# DDS_Module_r3.net
KiCad netlist of a schematic drawn in EAGLE
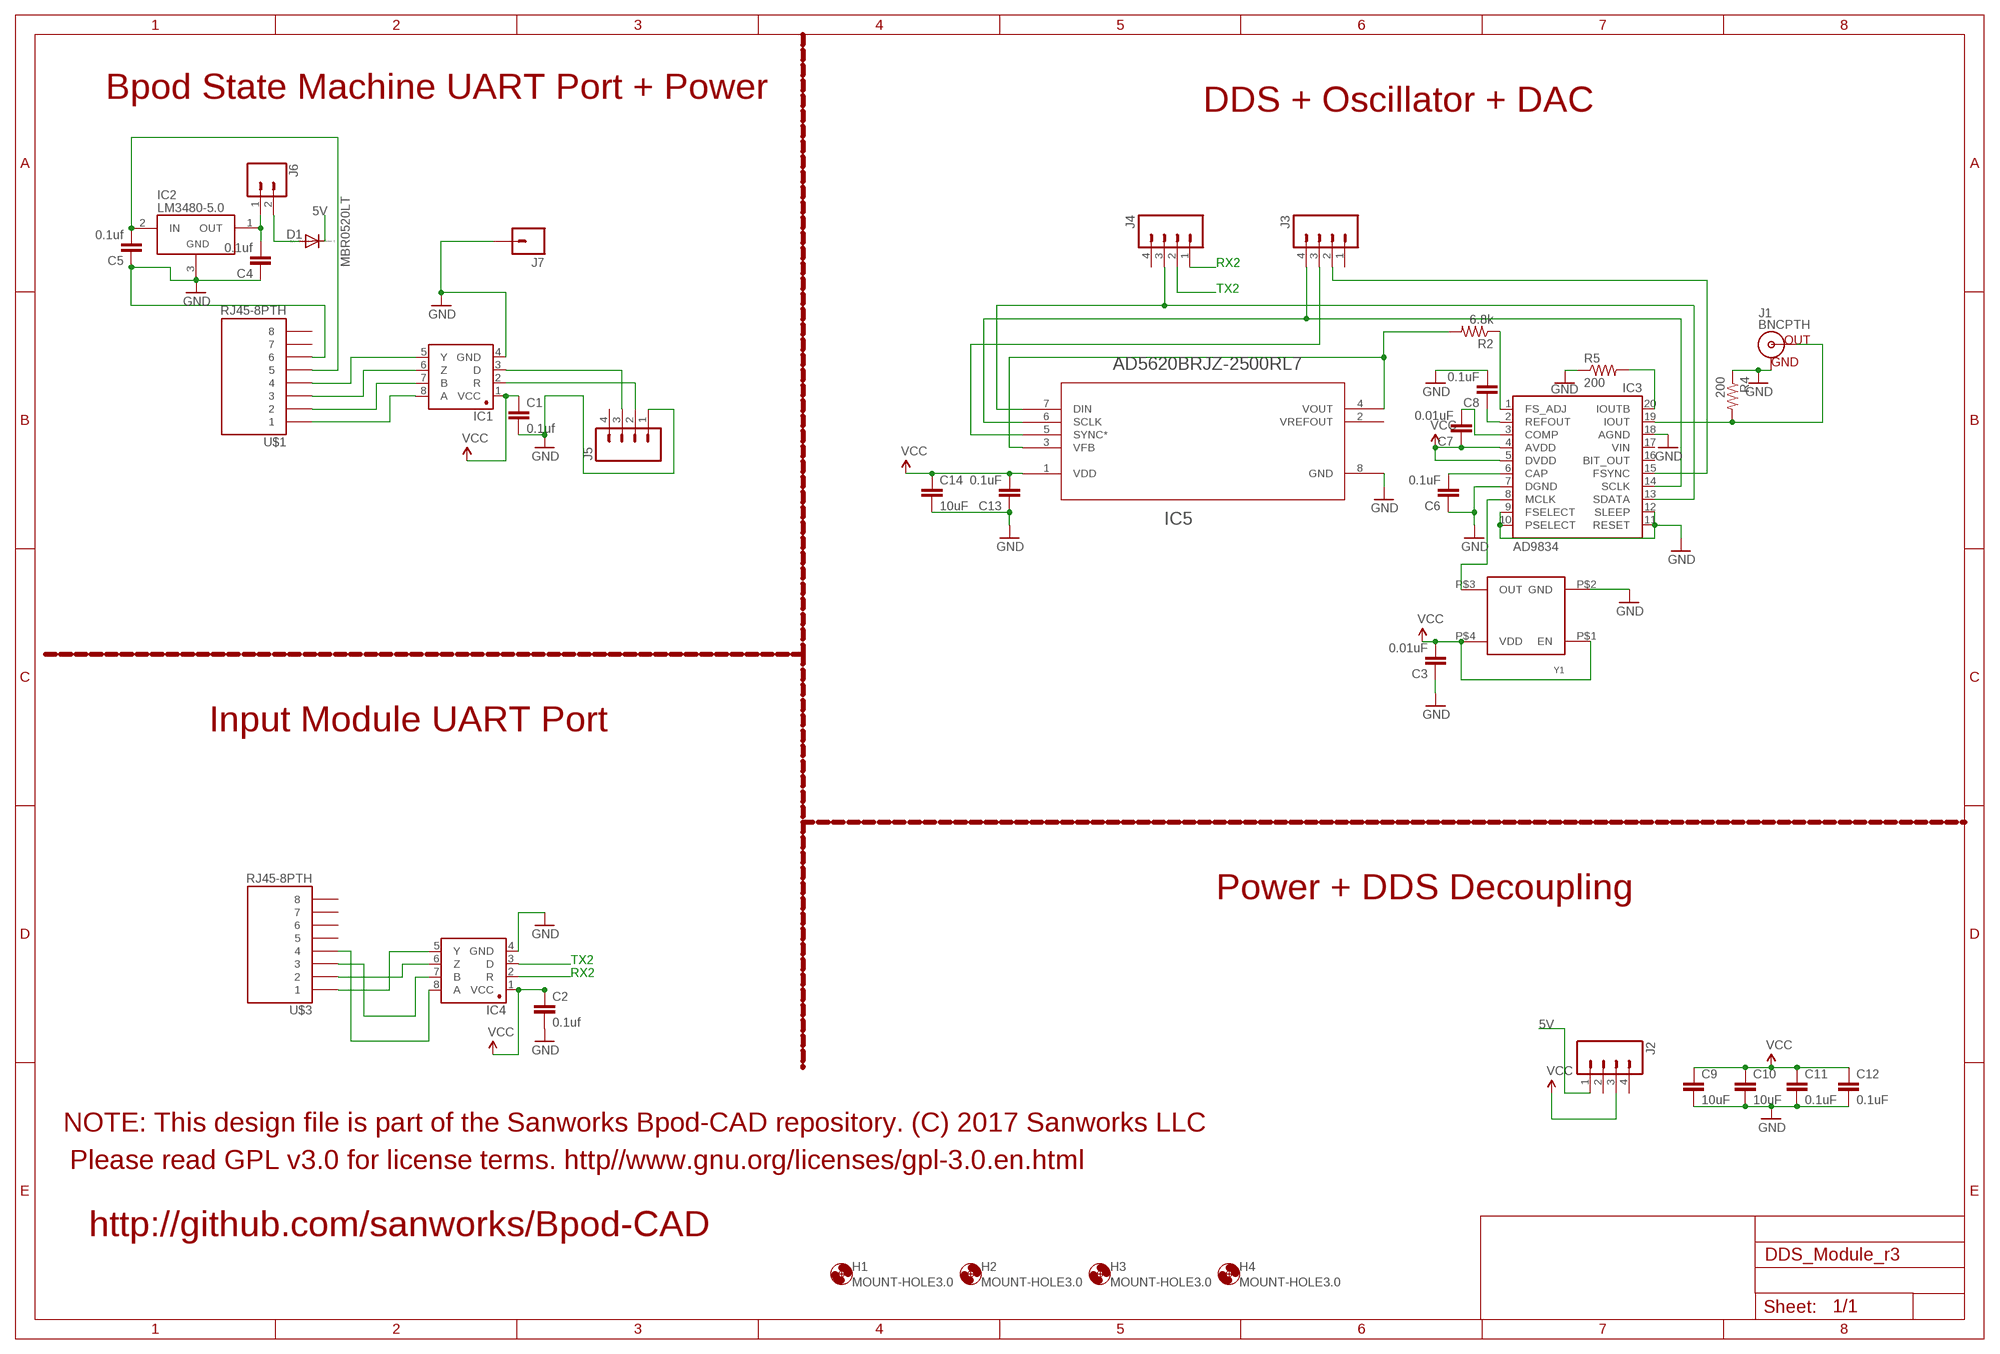
[diagram p0: schematic, sheet 1]

(export (version "E")
  (design (tool "Eeschema 10.0.6"))
  (components
    (comp (ref "C1")
      (value "0.1uf")
      (footprint "eagle-import:1206@1")
      (libsource (lib "eagle-import") (part "CAP1206"))
    )
    (comp (ref "C2")
      (value "0.1uf")
      (footprint "eagle-import:1206@1")
      (libsource (lib "eagle-import") (part "CAP1206"))
    )
    (comp (ref "C3")
      (value "0.01uF")
      (footprint "eagle-import:0805")
      (libsource (lib "eagle-import") (part "10UF-0805-10V-10%"))
    )
    (comp (ref "C4")
      (value "0.1uf")
      (footprint "eagle-import:1206@1")
      (libsource (lib "eagle-import") (part "CAP1206"))
    )
    (comp (ref "C5")
      (value "0.1uf")
      (footprint "eagle-import:1206@1")
      (libsource (lib "eagle-import") (part "CAP1206"))
    )
    (comp (ref "C6")
      (value "0.1uF")
      (footprint "eagle-import:0805")
      (libsource (lib "eagle-import") (part "10UF-0805-10V-10%"))
    )
    (comp (ref "C7")
      (value "0.01uF")
      (footprint "eagle-import:0805")
      (libsource (lib "eagle-import") (part "10UF-0805-10V-10%"))
    )
    (comp (ref "C8")
      (value "0.1uF")
      (footprint "eagle-import:0805")
      (libsource (lib "eagle-import") (part "10UF-0805-10V-10%"))
    )
    (comp (ref "C9")
      (value "10uF")
      (footprint "eagle-import:0805")
      (libsource (lib "eagle-import") (part "10UF-0805-10V-10%"))
    )
    (comp (ref "C10")
      (value "10uF")
      (footprint "eagle-import:0805")
      (libsource (lib "eagle-import") (part "10UF-0805-10V-10%"))
    )
    (comp (ref "C11")
      (value "0.1uF")
      (footprint "eagle-import:0805")
      (libsource (lib "eagle-import") (part "10UF-0805-10V-10%"))
    )
    (comp (ref "C12")
      (value "0.1uF")
      (footprint "eagle-import:0805")
      (libsource (lib "eagle-import") (part "10UF-0805-10V-10%"))
    )
    (comp (ref "C13")
      (value "0.1uF")
      (footprint "eagle-import:0805")
      (libsource (lib "eagle-import") (part "10UF-0805-10V-10%"))
    )
    (comp (ref "C14")
      (value "10uF")
      (footprint "eagle-import:0805")
      (libsource (lib "eagle-import") (part "10UF-0805-10V-10%"))
    )
    (comp (ref "D1")
      (value "MBR0520LT")
      (footprint "eagle-import:SOD123")
      (libsource (lib "eagle-import") (part "MBR0520LT"))
    )
    (comp (ref "H1")
      (value "MOUNT-HOLE3.0")
      (footprint "eagle-import:3,0")
      (libsource (lib "eagle-import") (part "MOUNT-HOLE3.0"))
    )
    (comp (ref "H2")
      (value "MOUNT-HOLE3.0")
      (footprint "eagle-import:3,0")
      (libsource (lib "eagle-import") (part "MOUNT-HOLE3.0"))
    )
    (comp (ref "H3")
      (value "MOUNT-HOLE3.0")
      (footprint "eagle-import:3,0")
      (libsource (lib "eagle-import") (part "MOUNT-HOLE3.0"))
    )
    (comp (ref "H4")
      (value "MOUNT-HOLE3.0")
      (footprint "eagle-import:3,0")
      (libsource (lib "eagle-import") (part "MOUNT-HOLE3.0"))
    )
    (comp (ref "IC1")
      (value "SN65HVD31DR")
      (footprint "eagle-import:SO08")
      (libsource (lib "eagle-import") (part "SN65HVD31DR"))
    )
    (comp (ref "IC2")
      (value "LM3480-5.0")
      (footprint "eagle-import:SOT-23-3")
      (libsource (lib "eagle-import") (part "LM3480-5.0"))
    )
    (comp (ref "IC3")
      (value "AD9834")
      (footprint "eagle-import:TSSOP20")
      (libsource (lib "eagle-import") (part "AD9834"))
    )
    (comp (ref "IC4")
      (value "SN65HVD31DR")
      (footprint "eagle-import:SO08")
      (libsource (lib "eagle-import") (part "SN65HVD31DR"))
    )
    (comp (ref "IC5")
      (value "AD5620BRJZ-2500RL7")
      (footprint "eagle-import:RJ_8")
      (fields (field (name "MANUFACTURER_PART_NUMBER") "AD5620BRJZ2500RL7"))
      (libsource (lib "eagle-import") (part "AD5620BRJZ-2500RL7"))
    )
    (comp (ref "J1")
      (value "BNCPTH")
      (footprint "eagle-import:BNC")
      (libsource (lib "eagle-import") (part "BNCPTH"))
    )
    (comp (ref "J2")
      (value "M04PTH")
      (footprint "eagle-import:1X04")
      (libsource (lib "eagle-import") (part "M04PTH"))
    )
    (comp (ref "J3")
      (value "M04PTH")
      (footprint "eagle-import:1X04")
      (libsource (lib "eagle-import") (part "M04PTH"))
    )
    (comp (ref "J4")
      (value "M04PTH")
      (footprint "eagle-import:1X04")
      (libsource (lib "eagle-import") (part "M04PTH"))
    )
    (comp (ref "J5")
      (value "M04PTH")
      (footprint "eagle-import:1X04")
      (libsource (lib "eagle-import") (part "M04PTH"))
    )
    (comp (ref "J6")
      (value "CONN_02")
      (footprint "eagle-import:1X02")
      (libsource (lib "eagle-import") (part "CONN_02"))
    )
    (comp (ref "J7")
      (value "M01PTH")
      (footprint "eagle-import:1X01")
      (libsource (lib "eagle-import") (part "M01PTH"))
    )
    (comp (ref "R2")
      (value "6.8k")
      (footprint "eagle-import:R0805")
      (libsource (lib "eagle-import") (part "R-US_R0805"))
    )
    (comp (ref "R4")
      (value "200")
      (footprint "eagle-import:R0805")
      (libsource (lib "eagle-import") (part "R-US_R0805"))
    )
    (comp (ref "R5")
      (value "200")
      (footprint "eagle-import:R0805")
      (libsource (lib "eagle-import") (part "R-US_R0805"))
    )
    (comp (ref "U$1")
      (value "RJ45-8PTH")
      (footprint "eagle-import:RJ45-8")
      (libsource (lib "eagle-import") (part "RJ45-8PTH"))
    )
    (comp (ref "U$3")
      (value "RJ45-8PTH")
      (footprint "eagle-import:RJ45-8")
      (libsource (lib "eagle-import") (part "RJ45-8PTH"))
    )
    (comp (ref "Y1")
      (value "ASE10MHZ")
      (footprint "eagle-import:ASE10MHZ")
      (libsource (lib "eagle-import") (part "ASE10MHZ"))
    )
  )
  (nets
    (net (code "1") (name "/5V") (class "Default")
      (node (ref "D1") (pin "C") (pinfunction "C_C") (pintype "passive"))
      (node (ref "J2") (pin "1") (pinfunction "1_1") (pintype "passive"))
    )
    (net (code "2") (name "/RX2") (class "Default")
      (node (ref "IC4") (pin "2") (pinfunction "R_2") (pintype "bidirectional"))
      (node (ref "J4") (pin "1") (pinfunction "1_1") (pintype "passive"))
    )
    (net (code "3") (name "/TX2") (class "Default")
      (node (ref "IC4") (pin "3") (pinfunction "D_3") (pintype "bidirectional"))
      (node (ref "J4") (pin "2") (pinfunction "2_2") (pintype "passive"))
    )
    (net (code "4") (name "GND") (class "Default")
      (node (ref "C1") (pin "2") (pinfunction "2_2") (pintype "passive"))
      (node (ref "C10") (pin "2") (pinfunction "2_2") (pintype "passive"))
      (node (ref "C11") (pin "2") (pinfunction "2_2") (pintype "passive"))
      (node (ref "C12") (pin "2") (pinfunction "2_2") (pintype "passive"))
      (node (ref "C13") (pin "1") (pinfunction "1_1") (pintype "passive"))
      (node (ref "C14") (pin "2") (pinfunction "2_2") (pintype "passive"))
      (node (ref "C2") (pin "2") (pinfunction "2_2") (pintype "passive"))
      (node (ref "C3") (pin "1") (pinfunction "1_1") (pintype "passive"))
      (node (ref "C4") (pin "1") (pinfunction "1_1") (pintype "passive"))
      (node (ref "C5") (pin "1") (pinfunction "1_1") (pintype "passive"))
      (node (ref "C6") (pin "1") (pinfunction "1_1") (pintype "passive"))
      (node (ref "C8") (pin "2") (pinfunction "2_2") (pintype "passive"))
      (node (ref "C9") (pin "2") (pinfunction "2_2") (pintype "passive"))
      (node (ref "IC1") (pin "4") (pinfunction "GND_4") (pintype "bidirectional"))
      (node (ref "IC2") (pin "3") (pinfunction "GND_3") (pintype "power_in"))
      (node (ref "IC3") (pin "10") (pinfunction "PSELECT_10") (pintype "bidirectional"))
      (node (ref "IC3") (pin "11") (pinfunction "RESET_11") (pintype "bidirectional"))
      (node (ref "IC3") (pin "12") (pinfunction "SLEEP_12") (pintype "bidirectional"))
      (node (ref "IC3") (pin "18") (pinfunction "AGND_18") (pintype "bidirectional"))
      (node (ref "IC3") (pin "7") (pinfunction "DGND_7") (pintype "bidirectional"))
      (node (ref "IC3") (pin "9") (pinfunction "FSELECT_9") (pintype "bidirectional"))
      (node (ref "IC4") (pin "4") (pinfunction "GND_4") (pintype "bidirectional"))
      (node (ref "IC5") (pin "8") (pinfunction "GND_8") (pintype "passive"))
      (node (ref "J1") (pin "GND") (pinfunction "GND_GND") (pintype "bidirectional"))
      (node (ref "J5") (pin "1") (pinfunction "1_1") (pintype "passive"))
      (node (ref "J7") (pin "1") (pinfunction "1_1") (pintype "passive"))
      (node (ref "R4") (pin "1") (pinfunction "1_1") (pintype "passive"))
      (node (ref "R5") (pin "1") (pinfunction "1_1") (pintype "passive"))
      (node (ref "U$1") (pin "6") (pinfunction "6_6") (pintype "bidirectional"))
      (node (ref "Y1") (pin "P$2") (pinfunction "GND_P$2") (pintype "bidirectional"))
    )
    (net (code "5") (name "Net-(D1-PadA)") (class "Default")
      (node (ref "D1") (pin "A") (pinfunction "A_A") (pintype "passive"))
      (node (ref "J6") (pin "2") (pinfunction "2_2") (pintype "passive"))
    )
    (net (code "6") (name "Net-(IC1-A)") (class "Default")
      (node (ref "IC1") (pin "8") (pinfunction "A_8") (pintype "bidirectional"))
      (node (ref "U$1") (pin "1") (pinfunction "1_1") (pintype "bidirectional"))
    )
    (net (code "7") (name "Net-(IC1-B)") (class "Default")
      (node (ref "IC1") (pin "7") (pinfunction "B_7") (pintype "bidirectional"))
      (node (ref "U$1") (pin "2") (pinfunction "2_2") (pintype "bidirectional"))
    )
    (net (code "8") (name "Net-(IC1-D)") (class "Default")
      (node (ref "IC1") (pin "3") (pinfunction "D_3") (pintype "bidirectional"))
      (node (ref "J5") (pin "3") (pinfunction "3_3") (pintype "passive"))
    )
    (net (code "9") (name "Net-(IC1-R)") (class "Default")
      (node (ref "IC1") (pin "2") (pinfunction "R_2") (pintype "bidirectional"))
      (node (ref "J5") (pin "2") (pinfunction "2_2") (pintype "passive"))
    )
    (net (code "10") (name "Net-(IC1-Y)") (class "Default")
      (node (ref "IC1") (pin "5") (pinfunction "Y_5") (pintype "bidirectional"))
      (node (ref "U$1") (pin "4") (pinfunction "4_4") (pintype "bidirectional"))
    )
    (net (code "11") (name "Net-(IC1-Z)") (class "Default")
      (node (ref "IC1") (pin "6") (pinfunction "Z_6") (pintype "bidirectional"))
      (node (ref "U$1") (pin "3") (pinfunction "3_3") (pintype "bidirectional"))
    )
    (net (code "12") (name "Net-(IC2-IN)") (class "Default")
      (node (ref "C5") (pin "2") (pinfunction "2_2") (pintype "passive"))
      (node (ref "IC2") (pin "2") (pinfunction "IN_2") (pintype "power_in"))
      (node (ref "U$1") (pin "5") (pinfunction "5_5") (pintype "bidirectional"))
    )
    (net (code "13") (name "Net-(IC2-OUT)") (class "Default")
      (node (ref "C4") (pin "2") (pinfunction "2_2") (pintype "passive"))
      (node (ref "IC2") (pin "1") (pinfunction "OUT_1") (pintype "power_in"))
      (node (ref "J6") (pin "1") (pinfunction "1_1") (pintype "passive"))
    )
    (net (code "14") (name "Net-(IC3-CAP)") (class "Default")
      (node (ref "C6") (pin "2") (pinfunction "2_2") (pintype "passive"))
      (node (ref "IC3") (pin "6") (pinfunction "CAP_6") (pintype "bidirectional"))
    )
    (net (code "15") (name "Net-(IC3-COMP)") (class "Default")
      (node (ref "C7") (pin "2") (pinfunction "2_2") (pintype "passive"))
      (node (ref "IC3") (pin "3") (pinfunction "COMP_3") (pintype "bidirectional"))
    )
    (net (code "16") (name "Net-(IC3-FSYNC)") (class "Default")
      (node (ref "IC3") (pin "15") (pinfunction "FSYNC_15") (pintype "bidirectional"))
      (node (ref "J3") (pin "2") (pinfunction "2_2") (pintype "passive"))
    )
    (net (code "17") (name "Net-(IC3-FS_ADJ)") (class "Default")
      (node (ref "IC3") (pin "1") (pinfunction "FS_ADJ_1") (pintype "bidirectional"))
      (node (ref "R2") (pin "1") (pinfunction "1_1") (pintype "passive"))
    )
    (net (code "18") (name "Net-(IC3-IOUT)") (class "Default")
      (node (ref "IC3") (pin "19") (pinfunction "IOUT_19") (pintype "bidirectional"))
      (node (ref "J1") (pin "S") (pinfunction "OUT_S") (pintype "bidirectional"))
      (node (ref "R4") (pin "2") (pinfunction "2_2") (pintype "passive"))
    )
    (net (code "19") (name "Net-(IC3-IOUTB)") (class "Default")
      (node (ref "IC3") (pin "20") (pinfunction "IOUTB_20") (pintype "bidirectional"))
      (node (ref "R5") (pin "2") (pinfunction "2_2") (pintype "passive"))
    )
    (net (code "20") (name "Net-(IC3-MCLK)") (class "Default")
      (node (ref "IC3") (pin "8") (pinfunction "MCLK_8") (pintype "bidirectional"))
      (node (ref "Y1") (pin "P$3") (pinfunction "OUT_P$3") (pintype "bidirectional"))
    )
    (net (code "21") (name "Net-(IC3-REFOUT)") (class "Default")
      (node (ref "C8") (pin "1") (pinfunction "1_1") (pintype "passive"))
      (node (ref "IC3") (pin "2") (pinfunction "REFOUT_2") (pintype "bidirectional"))
    )
    (net (code "22") (name "Net-(IC3-SCLK)") (class "Default")
      (node (ref "IC3") (pin "14") (pinfunction "SCLK_14") (pintype "bidirectional"))
      (node (ref "IC5") (pin "6") (pinfunction "SCLK_6") (pintype "passive"))
      (node (ref "J3") (pin "4") (pinfunction "4_4") (pintype "passive"))
    )
    (net (code "23") (name "Net-(IC3-SDATA)") (class "Default")
      (node (ref "IC3") (pin "13") (pinfunction "SDATA_13") (pintype "bidirectional"))
      (node (ref "IC5") (pin "7") (pinfunction "DIN_7") (pintype "passive"))
      (node (ref "J4") (pin "3") (pinfunction "3_3") (pintype "passive"))
    )
    (net (code "24") (name "Net-(IC4-A)") (class "Default")
      (node (ref "IC4") (pin "8") (pinfunction "A_8") (pintype "bidirectional"))
      (node (ref "U$3") (pin "4") (pinfunction "4_4") (pintype "bidirectional"))
    )
    (net (code "25") (name "Net-(IC4-B)") (class "Default")
      (node (ref "IC4") (pin "7") (pinfunction "B_7") (pintype "bidirectional"))
      (node (ref "U$3") (pin "3") (pinfunction "3_3") (pintype "bidirectional"))
    )
    (net (code "26") (name "Net-(IC4-Y)") (class "Default")
      (node (ref "IC4") (pin "5") (pinfunction "Y_5") (pintype "bidirectional"))
      (node (ref "U$3") (pin "1") (pinfunction "1_1") (pintype "bidirectional"))
    )
    (net (code "27") (name "Net-(IC4-Z)") (class "Default")
      (node (ref "IC4") (pin "6") (pinfunction "Z_6") (pintype "bidirectional"))
      (node (ref "U$3") (pin "2") (pinfunction "2_2") (pintype "bidirectional"))
    )
    (net (code "28") (name "Net-(IC5-SYNC*)") (class "Default")
      (node (ref "IC5") (pin "5") (pinfunction "SYNC*_5") (pintype "passive"))
      (node (ref "J3") (pin "3") (pinfunction "3_3") (pintype "passive"))
    )
    (net (code "29") (name "Net-(IC5-VFB)") (class "Default")
      (node (ref "IC5") (pin "3") (pinfunction "VFB_3") (pintype "passive"))
      (node (ref "IC5") (pin "4") (pinfunction "VOUT_4") (pintype "passive"))
      (node (ref "R2") (pin "2") (pinfunction "2_2") (pintype "passive"))
    )
    (net (code "30") (name "VCC") (class "Default")
      (node (ref "C1") (pin "1") (pinfunction "1_1") (pintype "passive"))
      (node (ref "C10") (pin "1") (pinfunction "1_1") (pintype "passive"))
      (node (ref "C11") (pin "1") (pinfunction "1_1") (pintype "passive"))
      (node (ref "C12") (pin "1") (pinfunction "1_1") (pintype "passive"))
      (node (ref "C13") (pin "2") (pinfunction "2_2") (pintype "passive"))
      (node (ref "C14") (pin "1") (pinfunction "1_1") (pintype "passive"))
      (node (ref "C2") (pin "1") (pinfunction "1_1") (pintype "passive"))
      (node (ref "C3") (pin "2") (pinfunction "2_2") (pintype "passive"))
      (node (ref "C7") (pin "1") (pinfunction "1_1") (pintype "passive"))
      (node (ref "C9") (pin "1") (pinfunction "1_1") (pintype "passive"))
      (node (ref "IC1") (pin "1") (pinfunction "VCC_1") (pintype "bidirectional"))
      (node (ref "IC3") (pin "4") (pinfunction "AVDD_4") (pintype "bidirectional"))
      (node (ref "IC3") (pin "5") (pinfunction "DVDD_5") (pintype "bidirectional"))
      (node (ref "IC4") (pin "1") (pinfunction "VCC_1") (pintype "bidirectional"))
      (node (ref "IC5") (pin "1") (pinfunction "VDD_1") (pintype "power_in"))
      (node (ref "J2") (pin "3") (pinfunction "3_3") (pintype "passive"))
      (node (ref "Y1") (pin "P$1") (pinfunction "EN_P$1") (pintype "bidirectional"))
      (node (ref "Y1") (pin "P$4") (pinfunction "VDD_P$4") (pintype "bidirectional"))
    )
    (net (code "31") (name "unconnected-(IC3-BIT_OUT-Pad16)") (class "Default")
      (node (ref "IC3") (pin "16") (pinfunction "BIT_OUT_16") (pintype "bidirectional"))
    )
    (net (code "32") (name "unconnected-(IC3-VIN-Pad17)") (class "Default")
      (node (ref "IC3") (pin "17") (pinfunction "VIN_17") (pintype "bidirectional"))
    )
    (net (code "33") (name "unconnected-(IC5-VREFOUT-Pad2)") (class "Default")
      (node (ref "IC5") (pin "2") (pinfunction "VREFOUT_2") (pintype "passive"))
    )
    (net (code "34") (name "unconnected-(J2-Pad2)") (class "Default")
      (node (ref "J2") (pin "2") (pinfunction "2_2") (pintype "passive"))
    )
    (net (code "35") (name "unconnected-(J2-Pad4)") (class "Default")
      (node (ref "J2") (pin "4") (pinfunction "4_4") (pintype "passive"))
    )
    (net (code "36") (name "unconnected-(J3-Pad1)") (class "Default")
      (node (ref "J3") (pin "1") (pinfunction "1_1") (pintype "passive"))
    )
    (net (code "37") (name "unconnected-(J4-Pad4)") (class "Default")
      (node (ref "J4") (pin "4") (pinfunction "4_4") (pintype "passive"))
    )
    (net (code "38") (name "unconnected-(J5-Pad4)") (class "Default")
      (node (ref "J5") (pin "4") (pinfunction "4_4") (pintype "passive"))
    )
    (net (code "39") (name "unconnected-(U$1-Pad7)") (class "Default")
      (node (ref "U$1") (pin "7") (pinfunction "7_7") (pintype "bidirectional"))
    )
    (net (code "40") (name "unconnected-(U$1-Pad8)") (class "Default")
      (node (ref "U$1") (pin "8") (pinfunction "8_8") (pintype "bidirectional"))
    )
    (net (code "41") (name "unconnected-(U$3-Pad5)") (class "Default")
      (node (ref "U$3") (pin "5") (pinfunction "5_5") (pintype "bidirectional"))
    )
    (net (code "42") (name "unconnected-(U$3-Pad6)") (class "Default")
      (node (ref "U$3") (pin "6") (pinfunction "6_6") (pintype "bidirectional"))
    )
    (net (code "43") (name "unconnected-(U$3-Pad7)") (class "Default")
      (node (ref "U$3") (pin "7") (pinfunction "7_7") (pintype "bidirectional"))
    )
    (net (code "44") (name "unconnected-(U$3-Pad8)") (class "Default")
      (node (ref "U$3") (pin "8") (pinfunction "8_8") (pintype "bidirectional"))
    )
  )
)
